# ENC15LED.net
KiCad netlist of a schematic drawn in EAGLE
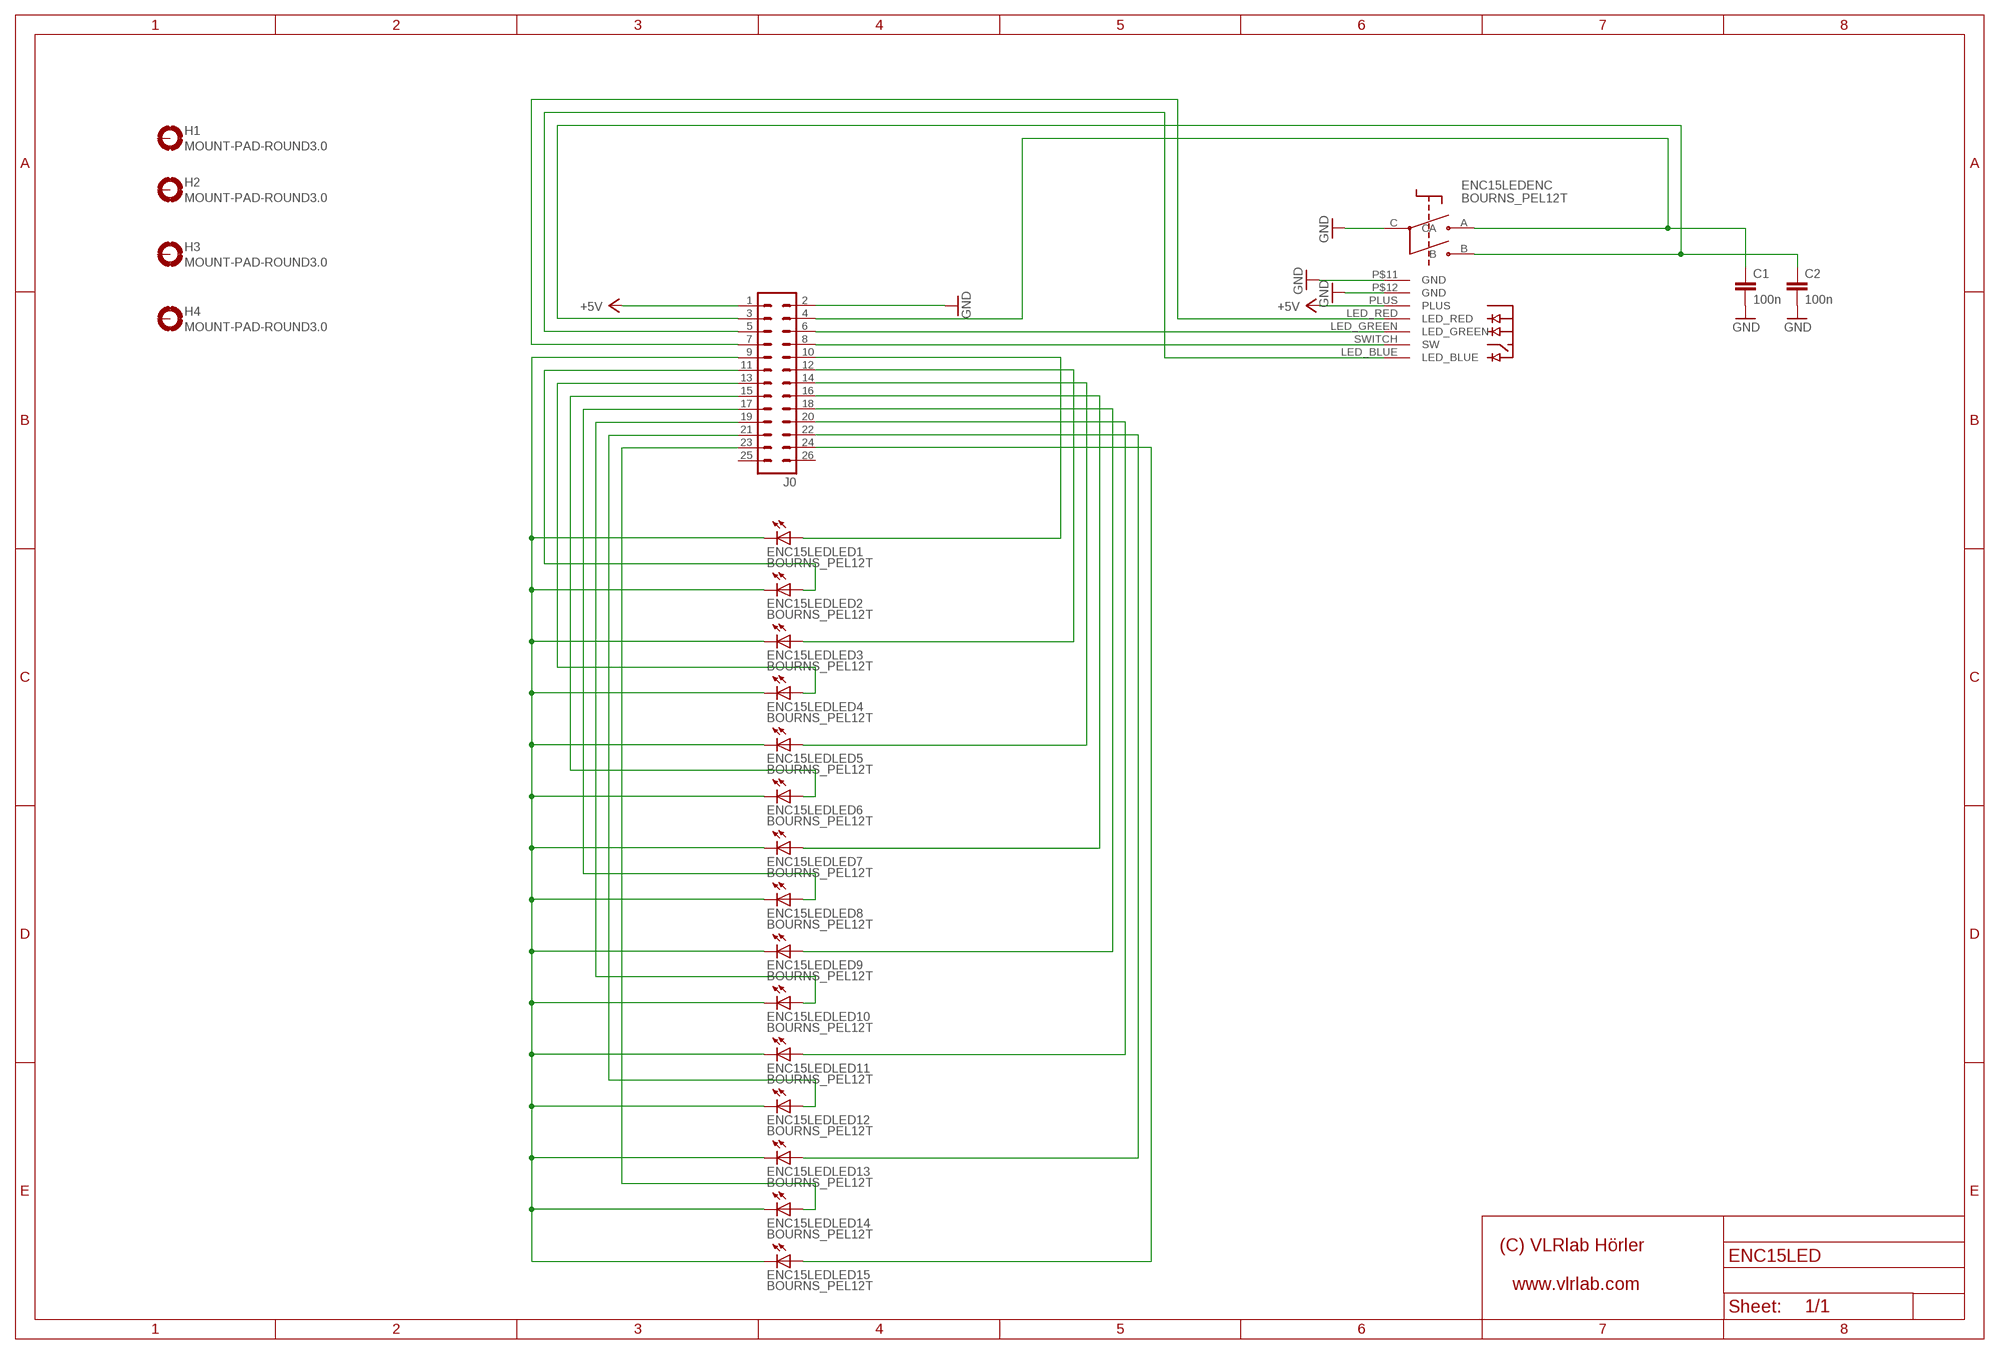
[diagram p0: schematic, sheet 1]

(export (version "E")
  (design (tool "Eeschema 10.0.6"))
  (components
    (comp (ref "C1")
      (value "100n")
      (footprint "eagle-import:C025-025X050")
      (libsource (lib "eagle-import") (part "C-EU025-025X050"))
    )
    (comp (ref "C2")
      (value "100n")
      (footprint "eagle-import:C025-025X050")
      (libsource (lib "eagle-import") (part "C-EU025-025X050"))
    )
    (comp (ref "ENC15LED")
      (value "BOURNS_PEL12T")
      (footprint "eagle-import:PEL12T_15LED-RING")
      (libsource (lib "eagle-import") (part "BOURNS_PEL12T_LED-RING"))
    )
    (comp (ref "H1")
      (value "MOUNT-PAD-ROUND3.0")
      (footprint "eagle-import:3,0-PAD")
      (libsource (lib "eagle-import") (part "MOUNT-PAD-ROUND3.0"))
    )
    (comp (ref "H2")
      (value "MOUNT-PAD-ROUND3.0")
      (footprint "eagle-import:3,0-PAD")
      (libsource (lib "eagle-import") (part "MOUNT-PAD-ROUND3.0"))
    )
    (comp (ref "H3")
      (value "MOUNT-PAD-ROUND3.0")
      (footprint "eagle-import:3,0-PAD")
      (libsource (lib "eagle-import") (part "MOUNT-PAD-ROUND3.0"))
    )
    (comp (ref "H4")
      (value "MOUNT-PAD-ROUND3.0")
      (footprint "eagle-import:3,0-PAD")
      (libsource (lib "eagle-import") (part "MOUNT-PAD-ROUND3.0"))
    )
    (comp (ref "J0")
      (value "ML26")
      (footprint "eagle-import:ML26")
      (libsource (lib "eagle-import") (part "ML26"))
    )
  )
  (nets
    (net (code "1") (name "+5V") (class "Default")
      (node (ref "ENC15LED") (pin "PLUS") (pinfunction "PLUS_PLUS") (pintype "bidirectional"))
      (node (ref "J0") (pin "1") (pinfunction "1_1") (pintype "passive"))
    )
    (net (code "2") (name "GND") (class "Default")
      (node (ref "C1") (pin "2") (pinfunction "2_2") (pintype "passive"))
      (node (ref "C2") (pin "2") (pinfunction "2_2") (pintype "passive"))
      (node (ref "ENC15LED") (pin "C") (pinfunction "C_C") (pintype "bidirectional"))
      (node (ref "ENC15LED") (pin "P$11") (pinfunction "GND_P$11") (pintype "bidirectional"))
      (node (ref "ENC15LED") (pin "P$12") (pinfunction "GND_P$12") (pintype "bidirectional"))
      (node (ref "J0") (pin "2") (pinfunction "2_2") (pintype "passive"))
    )
    (net (code "3") (name "Net-(C1-Pad1)") (class "Default")
      (node (ref "C1") (pin "1") (pinfunction "1_1") (pintype "passive"))
      (node (ref "ENC15LED") (pin "A") (pinfunction "A_A") (pintype "bidirectional"))
      (node (ref "J0") (pin "4") (pinfunction "4_4") (pintype "passive"))
    )
    (net (code "4") (name "Net-(C2-Pad1)") (class "Default")
      (node (ref "C2") (pin "1") (pinfunction "1_1") (pintype "passive"))
      (node (ref "ENC15LED") (pin "B") (pinfunction "B_B") (pintype "bidirectional"))
      (node (ref "J0") (pin "3") (pinfunction "3_3") (pintype "passive"))
    )
    (net (code "5") (name "Net-(ENC15LED-PadLED_BLUE)") (class "Default")
      (node (ref "ENC15LED") (pin "LED_BLUE") (pinfunction "LED_BLUE_LED_BLUE") (pintype "bidirectional"))
      (node (ref "J0") (pin "5") (pinfunction "5_5") (pintype "passive"))
    )
    (net (code "6") (name "Net-(ENC15LED-PadLED_GREEN)") (class "Default")
      (node (ref "ENC15LED") (pin "LED_GREEN") (pinfunction "LED_GREEN_LED_GREEN") (pintype "bidirectional"))
      (node (ref "J0") (pin "6") (pinfunction "6_6") (pintype "passive"))
    )
    (net (code "7") (name "Net-(ENC15LED-PadLED_RED)") (class "Default")
      (node (ref "ENC15LED") (pin "LED_RED") (pinfunction "LED_RED_LED_RED") (pintype "bidirectional"))
      (node (ref "J0") (pin "7") (pinfunction "7_7") (pintype "passive"))
    )
    (net (code "8") (name "Net-(ENC15LEDA-SW)") (class "Default")
      (node (ref "ENC15LED") (pin "SWITCH") (pinfunction "SW_SWITCH") (pintype "bidirectional"))
      (node (ref "J0") (pin "8") (pinfunction "8_8") (pintype "passive"))
    )
    (net (code "9") (name "Net-(ENC15LEDB-A)") (class "Default")
      (node (ref "ENC15LED") (pin "A01") (pinfunction "A_A01") (pintype "passive"))
      (node (ref "J0") (pin "10") (pinfunction "10_10") (pintype "passive"))
    )
    (net (code "10") (name "Net-(ENC15LEDB-C)") (class "Default")
      (node (ref "ENC15LED") (pin "K01") (pinfunction "C_K01") (pintype "passive"))
      (node (ref "ENC15LED") (pin "K02") (pinfunction "C_K02") (pintype "passive"))
      (node (ref "ENC15LED") (pin "K03") (pinfunction "C_K03") (pintype "passive"))
      (node (ref "ENC15LED") (pin "K04") (pinfunction "C_K04") (pintype "passive"))
      (node (ref "ENC15LED") (pin "K05") (pinfunction "C_K05") (pintype "passive"))
      (node (ref "ENC15LED") (pin "K06") (pinfunction "C_K06") (pintype "passive"))
      (node (ref "ENC15LED") (pin "K07") (pinfunction "C_K07") (pintype "passive"))
      (node (ref "ENC15LED") (pin "K08") (pinfunction "C_K08") (pintype "passive"))
      (node (ref "ENC15LED") (pin "K09") (pinfunction "C_K09") (pintype "passive"))
      (node (ref "ENC15LED") (pin "K10") (pinfunction "C_K10") (pintype "passive"))
      (node (ref "ENC15LED") (pin "K11") (pinfunction "C_K11") (pintype "passive"))
      (node (ref "ENC15LED") (pin "K12") (pinfunction "C_K12") (pintype "passive"))
      (node (ref "ENC15LED") (pin "K13") (pinfunction "C_K13") (pintype "passive"))
      (node (ref "ENC15LED") (pin "K14") (pinfunction "C_K14") (pintype "passive"))
      (node (ref "ENC15LED") (pin "K15") (pinfunction "C_K15") (pintype "passive"))
      (node (ref "J0") (pin "9") (pinfunction "9_9") (pintype "passive"))
    )
    (net (code "11") (name "Net-(ENC15LEDC-A)") (class "Default")
      (node (ref "ENC15LED") (pin "A10") (pinfunction "A_A10") (pintype "passive"))
      (node (ref "J0") (pin "19") (pinfunction "19_19") (pintype "passive"))
    )
    (net (code "12") (name "Net-(ENC15LEDD-A)") (class "Default")
      (node (ref "ENC15LED") (pin "A11") (pinfunction "A_A11") (pintype "passive"))
      (node (ref "J0") (pin "20") (pinfunction "20_20") (pintype "passive"))
    )
    (net (code "13") (name "Net-(ENC15LEDE-A)") (class "Default")
      (node (ref "ENC15LED") (pin "A12") (pinfunction "A_A12") (pintype "passive"))
      (node (ref "J0") (pin "21") (pinfunction "21_21") (pintype "passive"))
    )
    (net (code "14") (name "Net-(ENC15LEDF-A)") (class "Default")
      (node (ref "ENC15LED") (pin "A13") (pinfunction "A_A13") (pintype "passive"))
      (node (ref "J0") (pin "22") (pinfunction "22_22") (pintype "passive"))
    )
    (net (code "15") (name "Net-(ENC15LEDG-A)") (class "Default")
      (node (ref "ENC15LED") (pin "A14") (pinfunction "A_A14") (pintype "passive"))
      (node (ref "J0") (pin "23") (pinfunction "23_23") (pintype "passive"))
    )
    (net (code "16") (name "Net-(ENC15LEDH-A)") (class "Default")
      (node (ref "ENC15LED") (pin "A15") (pinfunction "A_A15") (pintype "passive"))
      (node (ref "J0") (pin "24") (pinfunction "24_24") (pintype "passive"))
    )
    (net (code "17") (name "Net-(ENC15LEDI-A)") (class "Default")
      (node (ref "ENC15LED") (pin "A02") (pinfunction "A_A02") (pintype "passive"))
      (node (ref "J0") (pin "11") (pinfunction "11_11") (pintype "passive"))
    )
    (net (code "18") (name "Net-(ENC15LEDJ-A)") (class "Default")
      (node (ref "ENC15LED") (pin "A03") (pinfunction "A_A03") (pintype "passive"))
      (node (ref "J0") (pin "12") (pinfunction "12_12") (pintype "passive"))
    )
    (net (code "19") (name "Net-(ENC15LEDK-A)") (class "Default")
      (node (ref "ENC15LED") (pin "A04") (pinfunction "A_A04") (pintype "passive"))
      (node (ref "J0") (pin "13") (pinfunction "13_13") (pintype "passive"))
    )
    (net (code "20") (name "Net-(ENC15LEDL-A)") (class "Default")
      (node (ref "ENC15LED") (pin "A05") (pinfunction "A_A05") (pintype "passive"))
      (node (ref "J0") (pin "14") (pinfunction "14_14") (pintype "passive"))
    )
    (net (code "21") (name "Net-(ENC15LEDM-A)") (class "Default")
      (node (ref "ENC15LED") (pin "A06") (pinfunction "A_A06") (pintype "passive"))
      (node (ref "J0") (pin "15") (pinfunction "15_15") (pintype "passive"))
    )
    (net (code "22") (name "Net-(ENC15LEDN-A)") (class "Default")
      (node (ref "ENC15LED") (pin "A07") (pinfunction "A_A07") (pintype "passive"))
      (node (ref "J0") (pin "16") (pinfunction "16_16") (pintype "passive"))
    )
    (net (code "23") (name "Net-(ENC15LEDO-A)") (class "Default")
      (node (ref "ENC15LED") (pin "A08") (pinfunction "A_A08") (pintype "passive"))
      (node (ref "J0") (pin "17") (pinfunction "17_17") (pintype "passive"))
    )
    (net (code "24") (name "Net-(ENC15LEDP-A)") (class "Default")
      (node (ref "ENC15LED") (pin "A09") (pinfunction "A_A09") (pintype "passive"))
      (node (ref "J0") (pin "18") (pinfunction "18_18") (pintype "passive"))
    )
    (net (code "25") (name "unconnected-(H1-MOUNT-PadB3,0)") (class "Default")
      (node (ref "H1") (pin "B3,0") (pinfunction "MOUNT_B3,0") (pintype "passive"))
    )
    (net (code "26") (name "unconnected-(H2-MOUNT-PadB3,0)") (class "Default")
      (node (ref "H2") (pin "B3,0") (pinfunction "MOUNT_B3,0") (pintype "passive"))
    )
    (net (code "27") (name "unconnected-(H3-MOUNT-PadB3,0)") (class "Default")
      (node (ref "H3") (pin "B3,0") (pinfunction "MOUNT_B3,0") (pintype "passive"))
    )
    (net (code "28") (name "unconnected-(H4-MOUNT-PadB3,0)") (class "Default")
      (node (ref "H4") (pin "B3,0") (pinfunction "MOUNT_B3,0") (pintype "passive"))
    )
    (net (code "29") (name "unconnected-(J0-Pad25)") (class "Default")
      (node (ref "J0") (pin "25") (pinfunction "25_25") (pintype "passive"))
    )
    (net (code "30") (name "unconnected-(J0-Pad26)") (class "Default")
      (node (ref "J0") (pin "26") (pinfunction "26_26") (pintype "passive"))
    )
  )
)
